# PressureTransducer.net
KiCad netlist of a schematic drawn in Altium Designer
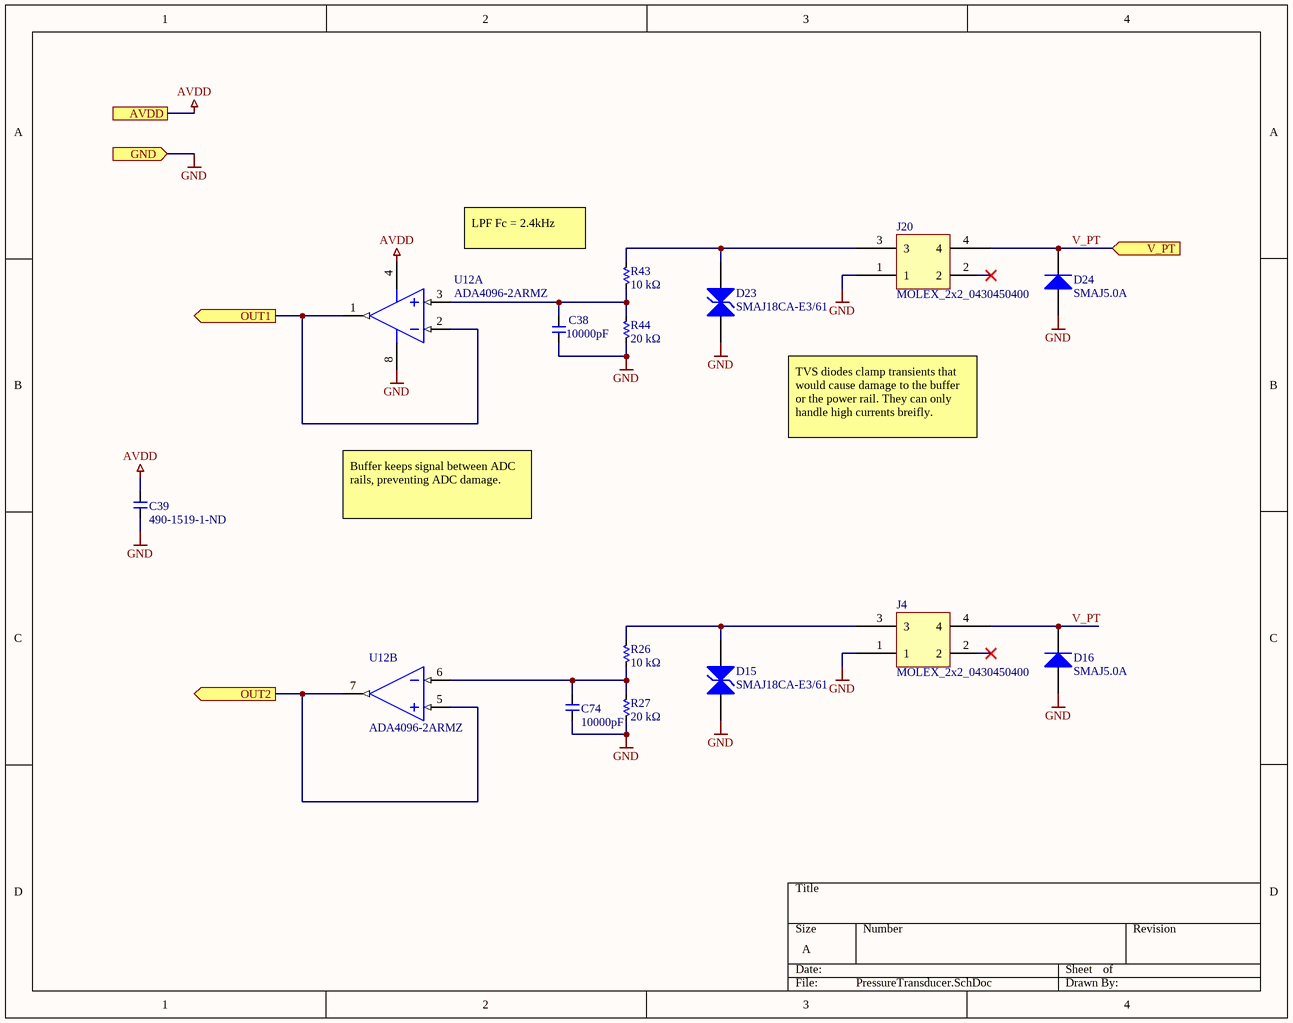
[diagram p0: PressureTransducer.SchDoc]

(export (version "E")
  (design (tool "Eeschema 10.0.6"))
  (components
    (comp (ref "C38")
      (value "490-1512-1-ND")
      (footprint "C0603")
      (description "CAP CER 0603 10000pF X7R 50V 10%")
      (fields
        (field (name "MANUFACTURER") "Murata Electronics North America")
        (field (name "CAPACITANCE (SHORTHAND)") "10000pF")
      )
      (libsource (lib "Stanford Student Space Initiative") (part "__template_cap"))
    )
    (comp (ref "C39")
      (value "490-1519-1-ND")
      (footprint "C0603")
      (description "CAP CER 0603 0.1µF X7R 50V 10%")
      (fields (field (name "MANUFACTURER") "Murata Electronics North America"))
      (libsource (lib "Stanford Student Space Initiative") (part "__template_cap"))
    )
    (comp (ref "C74")
      (value "490-1512-1-ND")
      (footprint "C0603")
      (description "CAP CER 0603 10000pF X7R 50V 10%")
      (fields
        (field (name "MANUFACTURER") "Murata Electronics North America")
        (field (name "CAPACITANCE (SHORTHAND)") "10000pF")
      )
      (libsource (lib "Stanford Student Space Initiative") (part "__template_cap"))
    )
    (comp (ref "D15")
      (value "SMAJ18CA-E3/61")
      (footprint "VISH-DO-214AC-2_M")
      (description "Diode TVS Single Bi-Dir 18V 400W 2-Pin SMA T/R")
      (libsource (lib "Stanford Student Space Initiative") (part "VISH-A1A2-2"))
    )
    (comp (ref "D16")
      (value "SMAJ5.0A")
      (footprint "BOUR-SMA-2_V")
      (description "BOURNS - SMAJ5.0A - TVS Diode, SMAJ Series, Unidirectional, 5 V, 9.2 V, DO-214AC (SMA), 2 Pins")
      (libsource (lib "Stanford Student Space Initiative") (part "D-AK-2"))
    )
    (comp (ref "D23")
      (value "SMAJ18CA-E3/61")
      (footprint "VISH-DO-214AC-2_M")
      (description "Diode TVS Single Bi-Dir 18V 400W 2-Pin SMA T/R")
      (libsource (lib "Stanford Student Space Initiative") (part "VISH-A1A2-2"))
    )
    (comp (ref "D24")
      (value "SMAJ5.0A")
      (footprint "BOUR-SMA-2_V")
      (description "BOURNS - SMAJ5.0A - TVS Diode, SMAJ Series, Unidirectional, 5 V, 9.2 V, DO-214AC (SMA), 2 Pins")
      (libsource (lib "Stanford Student Space Initiative") (part "D-AK-2"))
    )
    (comp (ref "J4")
      (value "MOLEX_2x2_0430450400")
      (footprint "MOLEX_2x2_0430450400")
      (description "MICROFIT CONN HEADER R/A 4POS 3MM")
      (libsource (lib "Stanford Student Space Initiative") (part "MOLEX_2x2_0430450400"))
    )
    (comp (ref "J20")
      (value "MOLEX_2x2_0430450400")
      (footprint "MOLEX_2x2_0430450400")
      (description "MICROFIT CONN HEADER R/A 4POS 3MM")
      (libsource (lib "Stanford Student Space Initiative") (part "MOLEX_2x2_0430450400"))
    )
    (comp (ref "R26")
      (value "311-10.0KHRCT-ND")
      (footprint "R0603")
      (description "RES SMD 10K OHM 1% 1/10W 0603")
      (fields
        (field (name "RESISTANCE") "10 kΩ")
        (field (name "MANUFACTURER PART NUMBER") "RC0603FR-0710KL")
        (field (name "MANUFACTURER") "Yageo")
      )
      (libsource (lib "Stanford Student Space Initiative") (part "__template_resistor"))
    )
    (comp (ref "R27")
      (value "311-20.0KHRCT-ND")
      (footprint "R0603")
      (description "RES SMD 20K OHM 1% 1/10W 0603")
      (fields
        (field (name "RESISTANCE") "20 kΩ")
        (field (name "MANUFACTURER PART NUMBER") "RC0603FR-0720KL")
        (field (name "MANUFACTURER") "Yageo")
      )
      (libsource (lib "Stanford Student Space Initiative") (part "__template_resistor"))
    )
    (comp (ref "R43")
      (value "311-10.0KHRCT-ND")
      (footprint "R0603")
      (description "RES SMD 10K OHM 1% 1/10W 0603")
      (fields
        (field (name "RESISTANCE") "10 kΩ")
        (field (name "MANUFACTURER PART NUMBER") "RC0603FR-0710KL")
        (field (name "MANUFACTURER") "Yageo")
      )
      (libsource (lib "Stanford Student Space Initiative") (part "__template_resistor"))
    )
    (comp (ref "R44")
      (value "311-20.0KHRCT-ND")
      (footprint "R0603")
      (description "RES SMD 20K OHM 1% 1/10W 0603")
      (fields
        (field (name "RESISTANCE") "20 kΩ")
        (field (name "MANUFACTURER PART NUMBER") "RC0603FR-0720KL")
        (field (name "MANUFACTURER") "Yageo")
      )
      (libsource (lib "Stanford Student Space Initiative") (part "__template_resistor"))
    )
    (comp (ref "U12")
      (value "ADA4096-2ARMZ")
      (footprint "ADI-RM-8_M")
      (description "Operational Amplifier, Dual, 501 kHz, 2, 0.25 V/ s, 3V to 30V, MSOP, 8 ;RoHS Compliant: Yes")
      (libsource (lib "Stanford Student Space Initiative") (part "ADI-ADA4000-2-X-8"))
    )
  )
  (nets
    (net (code "1") (name "/OUT1") (class "Default")
      (node (ref "U12") (pin "1") (pinfunction "OUT_A_1") (pintype "output"))
      (node (ref "U12") (pin "2") (pinfunction "-IN_A_2") (pintype "input"))
    )
    (net (code "2") (name "/OUT2") (class "Default")
      (node (ref "U12") (pin "5") (pinfunction "+IN_B_5") (pintype "input"))
      (node (ref "U12") (pin "7") (pinfunction "OUT_B_7") (pintype "output"))
    )
    (net (code "3") (name "/V_PT") (class "Default")
      (node (ref "D16") (pin "2") (pinfunction "K_2") (pintype "passive"))
      (node (ref "D24") (pin "2") (pinfunction "K_2") (pintype "passive"))
      (node (ref "J20") (pin "4") (pinfunction "4_4") (pintype "passive"))
      (node (ref "J4") (pin "4") (pinfunction "4_4") (pintype "passive"))
    )
    (net (code "4") (name "AVDD") (class "Default")
      (node (ref "C39") (pin "1") (pintype "passive"))
      (node (ref "U12") (pin "4") (pinfunction "-V_4") (pintype "power_in"))
    )
    (net (code "5") (name "GND") (class "Default")
      (node (ref "C38") (pin "2") (pintype "passive"))
      (node (ref "C39") (pin "2") (pintype "passive"))
      (node (ref "C74") (pin "2") (pintype "passive"))
      (node (ref "D15") (pin "1") (pinfunction "A1_1") (pintype "passive"))
      (node (ref "D16") (pin "1") (pinfunction "A_1") (pintype "passive"))
      (node (ref "D23") (pin "1") (pinfunction "A1_1") (pintype "passive"))
      (node (ref "D24") (pin "1") (pinfunction "A_1") (pintype "passive"))
      (node (ref "J20") (pin "1") (pinfunction "1_1") (pintype "passive"))
      (node (ref "J4") (pin "1") (pinfunction "1_1") (pintype "passive"))
      (node (ref "R27") (pin "1") (pinfunction "1_1") (pintype "passive"))
      (node (ref "R44") (pin "1") (pinfunction "1_1") (pintype "passive"))
      (node (ref "U12") (pin "8") (pinfunction "+V_8") (pintype "power_in"))
    )
    (net (code "6") (name "Net-(D15-A2)") (class "Default")
      (node (ref "D15") (pin "2") (pinfunction "A2_2") (pintype "passive"))
      (node (ref "J4") (pin "3") (pinfunction "3_3") (pintype "passive"))
      (node (ref "R26") (pin "2") (pinfunction "2_2") (pintype "passive"))
    )
    (net (code "7") (name "Net-(D23-A2)") (class "Default")
      (node (ref "D23") (pin "2") (pinfunction "A2_2") (pintype "passive"))
      (node (ref "J20") (pin "3") (pinfunction "3_3") (pintype "passive"))
      (node (ref "R43") (pin "2") (pinfunction "2_2") (pintype "passive"))
    )
    (net (code "8") (name "Net-(U12A-+IN_A)") (class "Default")
      (node (ref "C38") (pin "1") (pintype "passive"))
      (node (ref "R43") (pin "1") (pinfunction "1_1") (pintype "passive"))
      (node (ref "R44") (pin "2") (pinfunction "2_2") (pintype "passive"))
      (node (ref "U12") (pin "3") (pinfunction "+IN_A_3") (pintype "input"))
    )
    (net (code "9") (name "Net-(U12B--IN_B)") (class "Default")
      (node (ref "C74") (pin "1") (pintype "passive"))
      (node (ref "R26") (pin "1") (pinfunction "1_1") (pintype "passive"))
      (node (ref "R27") (pin "2") (pinfunction "2_2") (pintype "passive"))
      (node (ref "U12") (pin "6") (pinfunction "-IN_B_6") (pintype "input"))
    )
    (net (code "10") (name "unconnected-(J4-Pad2)") (class "Default")
      (node (ref "J4") (pin "2") (pinfunction "2_2") (pintype "passive+no_connect"))
    )
    (net (code "11") (name "unconnected-(J20-Pad2)") (class "Default")
      (node (ref "J20") (pin "2") (pinfunction "2_2") (pintype "passive+no_connect"))
    )
  )
)
